# Jacdac_Pressure_Sensor-RevB.net
KiCad netlist of a schematic drawn in EAGLE
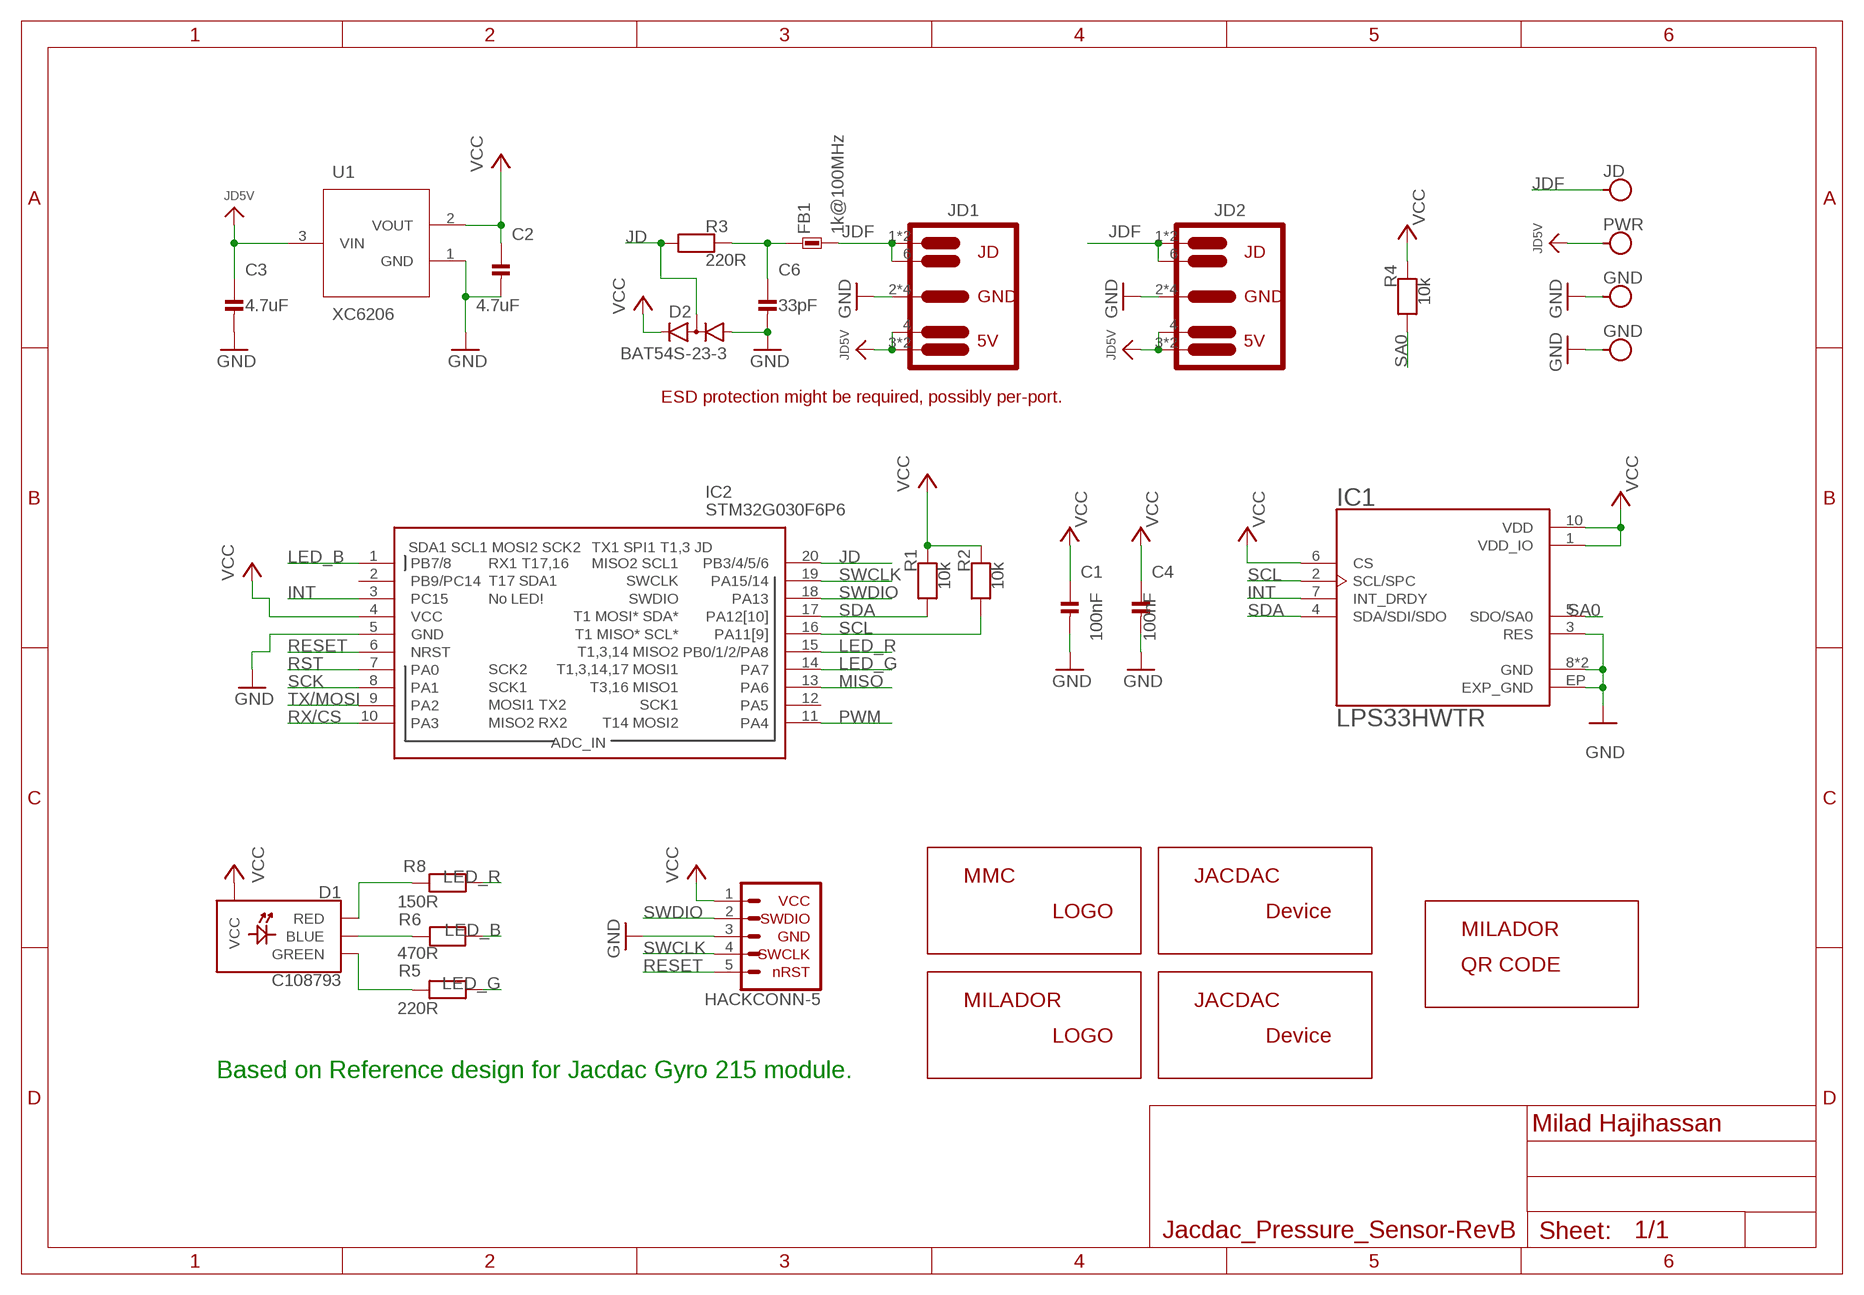
[diagram p0: schematic, sheet 1]

(export (version "E")
  (design (tool "Eeschema 10.0.6"))
  (components
    (comp (ref "C1")
      (value "100nF")
      (footprint "eagle-import:0402")
      (libsource (lib "eagle-import") (part "CAP_CERAMIC-0402"))
    )
    (comp (ref "C2")
      (value "4.7uF")
      (footprint "eagle-import:0402")
      (libsource (lib "eagle-import") (part "CAP_CERAMIC-0402"))
    )
    (comp (ref "C3")
      (value "4.7uF")
      (footprint "eagle-import:0402")
      (libsource (lib "eagle-import") (part "CAP_CERAMIC-0402"))
    )
    (comp (ref "C4")
      (value "100nF")
      (footprint "eagle-import:0402")
      (libsource (lib "eagle-import") (part "CAP_CERAMIC-0402"))
    )
    (comp (ref "C6")
      (value "33pF")
      (footprint "eagle-import:0402")
      (libsource (lib "eagle-import") (part "CAP_CERAMIC-0402"))
    )
    (comp (ref "D1")
      (value "C108793")
      (footprint "eagle-import:LED-RGB-2121")
      (libsource (lib "eagle-import") (part "LED-RGB-2121-CA"))
    )
    (comp (ref "D2")
      (value "BAT54S-23-3")
      (footprint "eagle-import:SOT23-3")
      (libsource (lib "eagle-import") (part "BAT54S-23-3"))
    )
    (comp (ref "FB1")
      (value "1k@100MHz")
      (footprint "eagle-import:0402")
      (libsource (lib "eagle-import") (part "FERRITE-BEAD-0402"))
    )
    (comp (ref "IC1")
      (value "LPS33HWTR")
      (footprint "eagle-import:PQFN60P330X330X290-11N")
      (fields (field (name "DIGI-KEY_PART_NUMBER") "497-17590-1-ND") (field (name "MF") "STMicroelectronics"))
      (libsource (lib "eagle-import") (part "LPS33HWTR"))
    )
    (comp (ref "IC2")
      (value "STM32G030F6P6")
      (footprint "eagle-import:SOP65P640X120-20N")
      (libsource (lib "eagle-import") (part "STM32G030F8P6"))
    )
    (comp (ref "J1")
      (value "JD")
      (footprint "eagle-import:M3-HOLE-DATA")
      (libsource (lib "eagle-import") (part "JACDAC-M3-DATA"))
    )
    (comp (ref "J2")
      (value "PWR")
      (footprint "eagle-import:M3-HOLE-PWR")
      (libsource (lib "eagle-import") (part "JACDAC-M3-PWR"))
    )
    (comp (ref "J3")
      (value "GND")
      (footprint "eagle-import:M3-HOLE-GND")
      (libsource (lib "eagle-import") (part "JACDAC-M3-GND"))
    )
    (comp (ref "J4")
      (value "GND")
      (footprint "eagle-import:M3-HOLE-GND")
      (libsource (lib "eagle-import") (part "JACDAC-M3-GND"))
    )
    (comp (ref "J5")
      (value "HACK-CONNECT-5")
      (footprint "eagle-import:HC5-22-62")
      (libsource (lib "eagle-import") (part "HACK-CONNECT-5"))
    )
    (comp (ref "JD1")
      (value "JACDAC-EDGE-OUTIE")
      (footprint "eagle-import:JD-EDGE-OUTIE")
      (libsource (lib "eagle-import") (part "JACDAC-EDGE-OUTIE"))
    )
    (comp (ref "JD2")
      (value "JACDAC-EDGE-OUTIE")
      (footprint "eagle-import:JD-EDGE-OUTIE")
      (libsource (lib "eagle-import") (part "JACDAC-EDGE-OUTIE"))
    )
    (comp (ref "LABEL_DEVICE")
      (value "MILADOR-JACDAC-DEVICE-PS")
      (footprint "eagle-import:JACDAC-PRESSURE-SENSOR")
      (libsource (lib "eagle-import") (part "MILADOR-JACDAC-DEVICE-PS"))
    )
    (comp (ref "LABEL_LOGO1")
      (value "MILADOR-LOGO-SM")
      (footprint "eagle-import:MILADOR_LOGO2")
      (libsource (lib "eagle-import") (part "MILADOR-LOGO-SM"))
    )
    (comp (ref "LABEL_LOGO2")
      (value "MMC_LOGO-XSM")
      (footprint "eagle-import:MMC_X-SMALL_LOGO")
      (libsource (lib "eagle-import") (part "MMC_LOGO-XSM"))
    )
    (comp (ref "LABEL_LPS33")
      (value "MILADOR-JACDAC-DEVICE-LPS33HW")
      (footprint "eagle-import:JACDAC-LPS33HW")
      (libsource (lib "eagle-import") (part "MILADOR-JACDAC-DEVICE-LPS33HW"))
    )
    (comp (ref "LABEL_QRCODE")
      (value "MILADOR-QR-CODE-JACDAC-GITHUB-PS")
      (footprint "eagle-import:MILADOR_QR_JACDAC_PS")
      (libsource (lib "eagle-import") (part "MILADOR-QR-CODE-JACDAC-GITHUB-PS"))
    )
    (comp (ref "R1")
      (value "10k")
      (footprint "eagle-import:0402")
      (libsource (lib "eagle-import") (part "RESISTOR-0402"))
    )
    (comp (ref "R2")
      (value "10k")
      (footprint "eagle-import:0402")
      (libsource (lib "eagle-import") (part "RESISTOR-0402"))
    )
    (comp (ref "R3")
      (value "220R")
      (footprint "eagle-import:0402")
      (libsource (lib "eagle-import") (part "RESISTOR-0402"))
    )
    (comp (ref "R4")
      (value "10k")
      (footprint "eagle-import:0402")
      (libsource (lib "eagle-import") (part "RESISTOR-0402"))
    )
    (comp (ref "R5")
      (value "220R")
      (footprint "eagle-import:0402")
      (libsource (lib "eagle-import") (part "RESISTOR-0402"))
    )
    (comp (ref "R6")
      (value "470R")
      (footprint "eagle-import:0402")
      (libsource (lib "eagle-import") (part "RESISTOR-0402"))
    )
    (comp (ref "R8")
      (value "150R")
      (footprint "eagle-import:0402")
      (libsource (lib "eagle-import") (part "RESISTOR-0402"))
    )
    (comp (ref "U1")
      (value "XC6206")
      (footprint "eagle-import:SOT23-3-W")
      (libsource (lib "eagle-import") (part "XC6206"))
    )
  )
  (nets
    (net (code "1") (name "/INT") (class "Default")
      (node (ref "IC1") (pin "7") (pinfunction "INT_DRDY_7") (pintype "bidirectional"))
      (node (ref "IC2") (pin "3") (pinfunction "PC15_3") (pintype "bidirectional"))
    )
    (net (code "2") (name "/JD") (class "Default")
      (node (ref "D2") (pin "3") (pinfunction "C1A2_3") (pintype "passive"))
      (node (ref "IC2") (pin "20") (pinfunction "PB3/4/5/6_20") (pintype "bidirectional"))
      (node (ref "R3") (pin "1") (pinfunction "1_1") (pintype "passive"))
    )
    (net (code "3") (name "/JDF") (class "Default")
      (node (ref "FB1") (pin "2") (pinfunction "2_2") (pintype "passive"))
      (node (ref "J1") (pin "H") (pinfunction "P$1_H") (pintype "bidirectional"))
      (node (ref "JD1") (pin "1") (pinfunction "2_1") (pintype "bidirectional"))
      (node (ref "JD1") (pin "6") (pinfunction "6_6") (pintype "bidirectional"))
      (node (ref "JD1") (pin "P$3") (pinfunction "2_P$3") (pintype "bidirectional"))
      (node (ref "JD2") (pin "1") (pinfunction "2_1") (pintype "bidirectional"))
      (node (ref "JD2") (pin "6") (pinfunction "6_6") (pintype "bidirectional"))
      (node (ref "JD2") (pin "P$3") (pinfunction "2_P$3") (pintype "bidirectional"))
    )
    (net (code "4") (name "/LED_B") (class "Default")
      (node (ref "IC2") (pin "1") (pinfunction "PB7/8_1") (pintype "input"))
      (node (ref "R6") (pin "1") (pinfunction "1_1") (pintype "passive"))
    )
    (net (code "5") (name "/LED_G") (class "Default")
      (node (ref "IC2") (pin "14") (pinfunction "PA7_14") (pintype "bidirectional"))
      (node (ref "R5") (pin "1") (pinfunction "1_1") (pintype "passive"))
    )
    (net (code "6") (name "/LED_R") (class "Default")
      (node (ref "IC2") (pin "15") (pinfunction "PB0/1/2/PA8_15") (pintype "input"))
      (node (ref "R8") (pin "1") (pinfunction "1_1") (pintype "passive"))
    )
    (net (code "7") (name "/MISO") (class "Default")
      (node (ref "IC2") (pin "13") (pinfunction "PA6_13") (pintype "bidirectional"))
    )
    (net (code "8") (name "/PWM") (class "Default")
      (node (ref "IC2") (pin "11") (pinfunction "PA4_11") (pintype "bidirectional"))
    )
    (net (code "9") (name "/RESET") (class "Default")
      (node (ref "IC2") (pin "6") (pinfunction "NRST_6") (pintype "bidirectional"))
      (node (ref "J5") (pin "5") (pinfunction "NRST_5") (pintype "bidirectional"))
    )
    (net (code "10") (name "/RST") (class "Default")
      (node (ref "IC2") (pin "7") (pinfunction "PA0_7") (pintype "bidirectional"))
    )
    (net (code "11") (name "/RX{slash}CS") (class "Default")
      (node (ref "IC2") (pin "10") (pinfunction "PA3_10") (pintype "bidirectional"))
    )
    (net (code "12") (name "/SA0") (class "Default")
      (node (ref "IC1") (pin "5") (pinfunction "SDO/SA0_5") (pintype "output"))
      (node (ref "R4") (pin "1") (pinfunction "1_1") (pintype "passive"))
    )
    (net (code "13") (name "/SCK") (class "Default")
      (node (ref "IC2") (pin "8") (pinfunction "PA1_8") (pintype "bidirectional"))
    )
    (net (code "14") (name "/SCL") (class "Default")
      (node (ref "IC1") (pin "2") (pinfunction "SCL/SPC_2") (pintype "input"))
      (node (ref "IC2") (pin "16") (pinfunction "PA11[9]_16") (pintype "input"))
      (node (ref "R2") (pin "1") (pinfunction "1_1") (pintype "passive"))
    )
    (net (code "15") (name "/SDA") (class "Default")
      (node (ref "IC1") (pin "4") (pinfunction "SDA/SDI/SDO_4") (pintype "bidirectional"))
      (node (ref "IC2") (pin "17") (pinfunction "PA12[10]_17") (pintype "bidirectional"))
      (node (ref "R1") (pin "1") (pinfunction "1_1") (pintype "passive"))
    )
    (net (code "16") (name "/SWCLK") (class "Default")
      (node (ref "IC2") (pin "19") (pinfunction "PA15/14_19") (pintype "bidirectional"))
      (node (ref "J5") (pin "4") (pinfunction "SWCLK_4") (pintype "input"))
    )
    (net (code "17") (name "/SWDIO") (class "Default")
      (node (ref "IC2") (pin "18") (pinfunction "PA13_18") (pintype "bidirectional"))
      (node (ref "J5") (pin "2") (pinfunction "SWDIO_2") (pintype "input"))
    )
    (net (code "18") (name "/TX{slash}MOSI") (class "Default")
      (node (ref "IC2") (pin "9") (pinfunction "PA2_9") (pintype "bidirectional"))
    )
    (net (code "19") (name "GND") (class "Default")
      (node (ref "C1") (pin "2") (pinfunction "2_2") (pintype "passive"))
      (node (ref "C2") (pin "2") (pinfunction "2_2") (pintype "passive"))
      (node (ref "C3") (pin "2") (pinfunction "2_2") (pintype "passive"))
      (node (ref "C4") (pin "2") (pinfunction "2_2") (pintype "passive"))
      (node (ref "C6") (pin "2") (pinfunction "2_2") (pintype "passive"))
      (node (ref "D2") (pin "1") (pinfunction "A1_1") (pintype "passive"))
      (node (ref "IC1") (pin "3") (pinfunction "RES_3") (pintype "passive"))
      (node (ref "IC1") (pin "8") (pinfunction "GND_8") (pintype "power_in"))
      (node (ref "IC1") (pin "9") (pinfunction "GND_9") (pintype "power_in"))
      (node (ref "IC1") (pin "EP") (pinfunction "EXP_GND_EP") (pintype "power_in"))
      (node (ref "IC2") (pin "5") (pinfunction "GND_5") (pintype "power_in"))
      (node (ref "J3") (pin "H") (pinfunction "P$1_H") (pintype "bidirectional"))
      (node (ref "J4") (pin "H") (pinfunction "P$1_H") (pintype "bidirectional"))
      (node (ref "J5") (pin "3") (pinfunction "GND_3") (pintype "power_in"))
      (node (ref "JD1") (pin "2") (pinfunction "1_2") (pintype "power_in"))
      (node (ref "JD1") (pin "5") (pinfunction "1_5") (pintype "power_in"))
      (node (ref "JD1") (pin "P$2") (pinfunction "1_P$2") (pintype "power_in"))
      (node (ref "JD1") (pin "P$4") (pinfunction "1_P$4") (pintype "power_in"))
      (node (ref "JD2") (pin "2") (pinfunction "1_2") (pintype "power_in"))
      (node (ref "JD2") (pin "5") (pinfunction "1_5") (pintype "power_in"))
      (node (ref "JD2") (pin "P$2") (pinfunction "1_P$2") (pintype "power_in"))
      (node (ref "JD2") (pin "P$4") (pinfunction "1_P$4") (pintype "power_in"))
      (node (ref "U1") (pin "1") (pinfunction "GND_1") (pintype "passive"))
    )
    (net (code "20") (name "JD5V") (class "Default")
      (node (ref "C3") (pin "1") (pinfunction "1_1") (pintype "passive"))
      (node (ref "J2") (pin "H") (pinfunction "P$1_H") (pintype "bidirectional"))
      (node (ref "JD1") (pin "3") (pinfunction "3_3") (pintype "power_in"))
      (node (ref "JD1") (pin "4") (pinfunction "4_4") (pintype "power_in"))
      (node (ref "JD1") (pin "P$1") (pinfunction "3_P$1") (pintype "power_in"))
      (node (ref "JD2") (pin "3") (pinfunction "3_3") (pintype "power_in"))
      (node (ref "JD2") (pin "4") (pinfunction "4_4") (pintype "power_in"))
      (node (ref "JD2") (pin "P$1") (pinfunction "3_P$1") (pintype "power_in"))
      (node (ref "U1") (pin "3") (pinfunction "VIN_3") (pintype "input"))
    )
    (net (code "21") (name "Net-(C6-Pad1)") (class "Default")
      (node (ref "C6") (pin "1") (pinfunction "1_1") (pintype "passive"))
      (node (ref "FB1") (pin "1") (pinfunction "1_1") (pintype "passive"))
      (node (ref "R3") (pin "2") (pinfunction "2_2") (pintype "passive"))
    )
    (net (code "22") (name "Net-(D1-BLUE)") (class "Default")
      (node (ref "D1") (pin "B-") (pinfunction "BLUE_B-") (pintype "bidirectional"))
      (node (ref "R6") (pin "2") (pinfunction "2_2") (pintype "passive"))
    )
    (net (code "23") (name "Net-(D1-GREEN)") (class "Default")
      (node (ref "D1") (pin "G-") (pinfunction "GREEN_G-") (pintype "bidirectional"))
      (node (ref "R5") (pin "2") (pinfunction "2_2") (pintype "passive"))
    )
    (net (code "24") (name "Net-(D1-RED)") (class "Default")
      (node (ref "D1") (pin "R-") (pinfunction "RED_R-") (pintype "bidirectional"))
      (node (ref "R8") (pin "2") (pinfunction "2_2") (pintype "passive"))
    )
    (net (code "25") (name "VCC") (class "Default")
      (node (ref "C1") (pin "1") (pinfunction "1_1") (pintype "passive"))
      (node (ref "C2") (pin "1") (pinfunction "1_1") (pintype "passive"))
      (node (ref "C4") (pin "1") (pinfunction "1_1") (pintype "passive"))
      (node (ref "D1") (pin "PLUS") (pinfunction "VCC_PLUS") (pintype "bidirectional"))
      (node (ref "D2") (pin "2") (pinfunction "C2_2") (pintype "passive"))
      (node (ref "IC1") (pin "1") (pinfunction "VDD_IO_1") (pintype "power_in"))
      (node (ref "IC1") (pin "10") (pinfunction "VDD_10") (pintype "power_in"))
      (node (ref "IC1") (pin "6") (pinfunction "CS_6") (pintype "bidirectional"))
      (node (ref "IC2") (pin "4") (pinfunction "VCC_4") (pintype "power_in"))
      (node (ref "J5") (pin "1") (pinfunction "VCC_1") (pintype "passive"))
      (node (ref "R1") (pin "2") (pinfunction "2_2") (pintype "passive"))
      (node (ref "R2") (pin "2") (pinfunction "2_2") (pintype "passive"))
      (node (ref "R4") (pin "2") (pinfunction "2_2") (pintype "passive"))
      (node (ref "U1") (pin "2") (pinfunction "VOUT_2") (pintype "power_in"))
    )
    (net (code "26") (name "unconnected-(IC2-PA5-Pad12)") (class "Default")
      (node (ref "IC2") (pin "12") (pinfunction "PA5_12") (pintype "bidirectional"))
    )
    (net (code "27") (name "unconnected-(IC2-PB9{slash}PC14-Pad2)") (class "Default")
      (node (ref "IC2") (pin "2") (pinfunction "PB9/PC14_2") (pintype "bidirectional"))
    )
  )
)
